# ESP8266-01-DHT11_V3.net
KiCad netlist of a schematic drawn in EAGLE
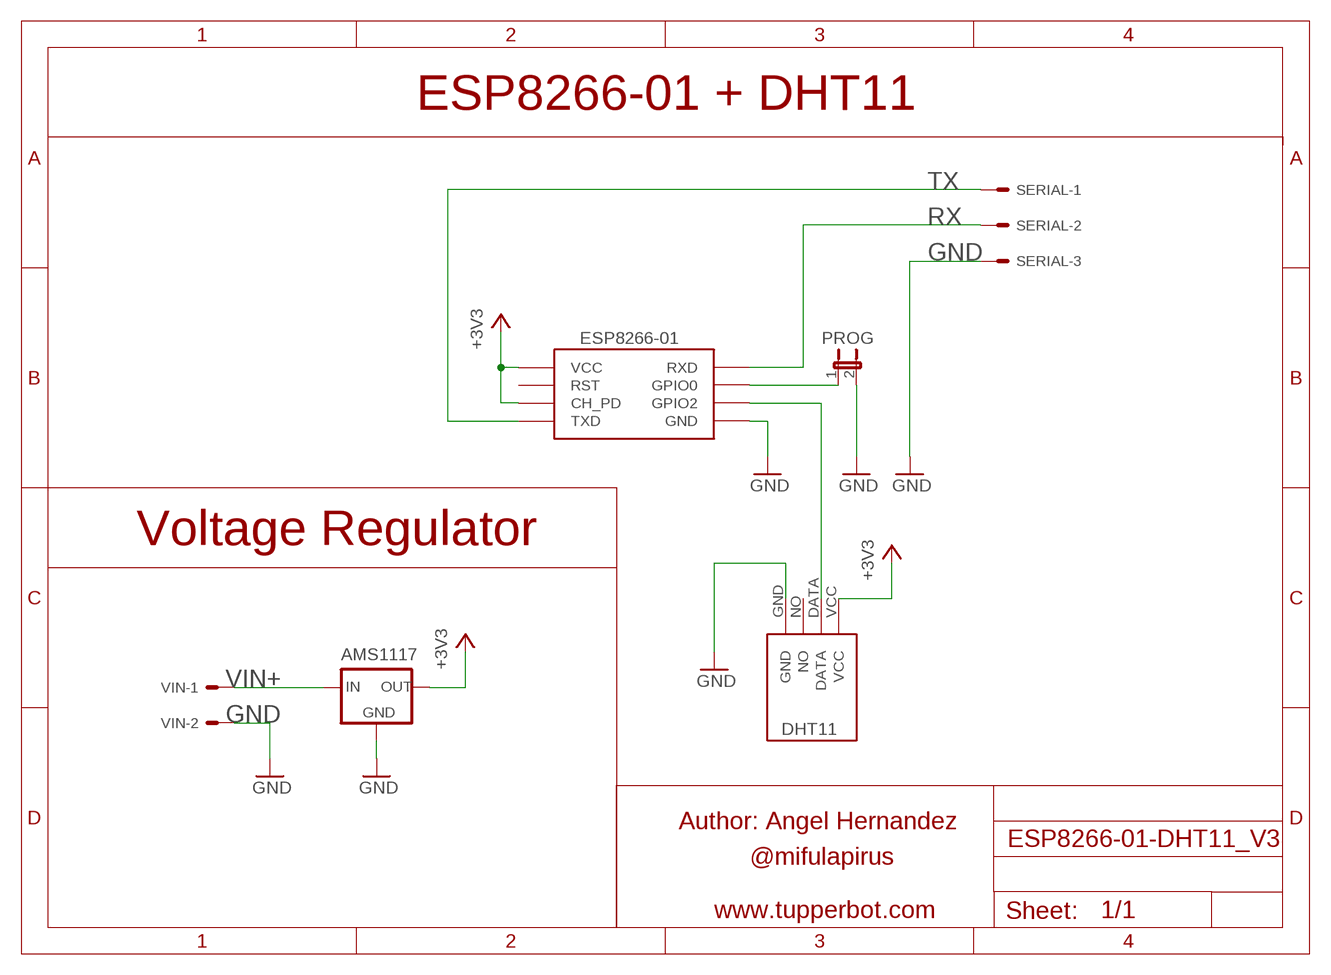
[diagram p0: schematic, sheet 1]

(export (version "E")
  (design (tool "Eeschema 10.0.6"))
  (components
    (comp (ref "AMS1117")
      (value "LM1117")
      (footprint "eagle-import:SOT223")
      (libsource (lib "eagle-import") (part "LM1117"))
    )
    (comp (ref "ESP8266-01")
      (value "ESP-01")
      (footprint "eagle-import:ESP-01")
      (libsource (lib "eagle-import") (part "ESP-01"))
    )
    (comp (ref "PROG")
      (value "JP1E")
      (footprint "eagle-import:JP1")
      (libsource (lib "eagle-import") (part "JP1E"))
    )
    (comp (ref "SERIAL")
      (value "22-27-2031-03")
      (footprint "eagle-import:6410-03")
      (libsource (lib "eagle-import") (part "22-?-0327-2031"))
    )
    (comp (ref "U$2")
      (value "DHT11-PION.")
      (footprint "eagle-import:DHT11-PION.")
      (libsource (lib "eagle-import") (part "DHT11-PION."))
    )
    (comp (ref "VIN")
      (value "22-27-2021-02")
      (footprint "eagle-import:6410-02")
      (libsource (lib "eagle-import") (part "22-?-0227-2021"))
    )
  )
  (nets
    (net (code "1") (name "+3V3") (class "Default")
      (node (ref "AMS1117") (pin "2") (pinfunction "OUT_2") (pintype "passive"))
      (node (ref "ESP8266-01") (pin "CH_PD") (pinfunction "CH_PD_CH_PD") (pintype "bidirectional"))
      (node (ref "ESP8266-01") (pin "VCC") (pinfunction "VCC_VCC") (pintype "bidirectional"))
      (node (ref "U$2") (pin "VCC") (pinfunction "VCC_VCC") (pintype "bidirectional"))
    )
    (net (code "2") (name "/RX") (class "Default")
      (node (ref "ESP8266-01") (pin "RX") (pinfunction "RXD_RX") (pintype "bidirectional"))
      (node (ref "SERIAL") (pin "2") (pinfunction "S_2") (pintype "passive"))
    )
    (net (code "3") (name "/TX") (class "Default")
      (node (ref "ESP8266-01") (pin "TX") (pinfunction "TXD_TX") (pintype "bidirectional"))
      (node (ref "SERIAL") (pin "1") (pinfunction "S_1") (pintype "passive"))
    )
    (net (code "4") (name "/VIN+") (class "Default")
      (node (ref "AMS1117") (pin "3") (pinfunction "IN_3") (pintype "input"))
      (node (ref "VIN") (pin "1") (pinfunction "S_1") (pintype "passive"))
    )
    (net (code "5") (name "GND") (class "Default")
      (node (ref "AMS1117") (pin "1") (pinfunction "GND_1") (pintype "input"))
      (node (ref "ESP8266-01") (pin "GND") (pinfunction "GND_GND") (pintype "bidirectional"))
      (node (ref "PROG") (pin "2") (pinfunction "2_2") (pintype "passive"))
      (node (ref "SERIAL") (pin "3") (pinfunction "S_3") (pintype "passive"))
      (node (ref "U$2") (pin "GND") (pinfunction "GND_GND") (pintype "bidirectional"))
      (node (ref "VIN") (pin "2") (pinfunction "S_2") (pintype "passive"))
    )
    (net (code "6") (name "Net-(ESP8266-01-PadGPIO0)") (class "Default")
      (node (ref "ESP8266-01") (pin "GPIO0") (pinfunction "GPIO0_GPIO0") (pintype "bidirectional"))
      (node (ref "PROG") (pin "1") (pinfunction "1_1") (pintype "passive"))
    )
    (net (code "7") (name "Net-(ESP8266-01-PadGPIO2)") (class "Default")
      (node (ref "ESP8266-01") (pin "GPIO2") (pinfunction "GPIO2_GPIO2") (pintype "bidirectional"))
      (node (ref "U$2") (pin "DATA") (pinfunction "DATA_DATA") (pintype "bidirectional"))
    )
    (net (code "8") (name "unconnected-(ESP8266-01-PadRST)") (class "Default")
      (node (ref "ESP8266-01") (pin "RST") (pinfunction "RST_RST") (pintype "bidirectional"))
    )
    (net (code "9") (name "unconnected-(U$2-PadNO)") (class "Default")
      (node (ref "U$2") (pin "NO") (pinfunction "NO_NO") (pintype "bidirectional"))
    )
  )
)
